# taktik.net
KiCad netlist of a schematic drawn in Altium Designer
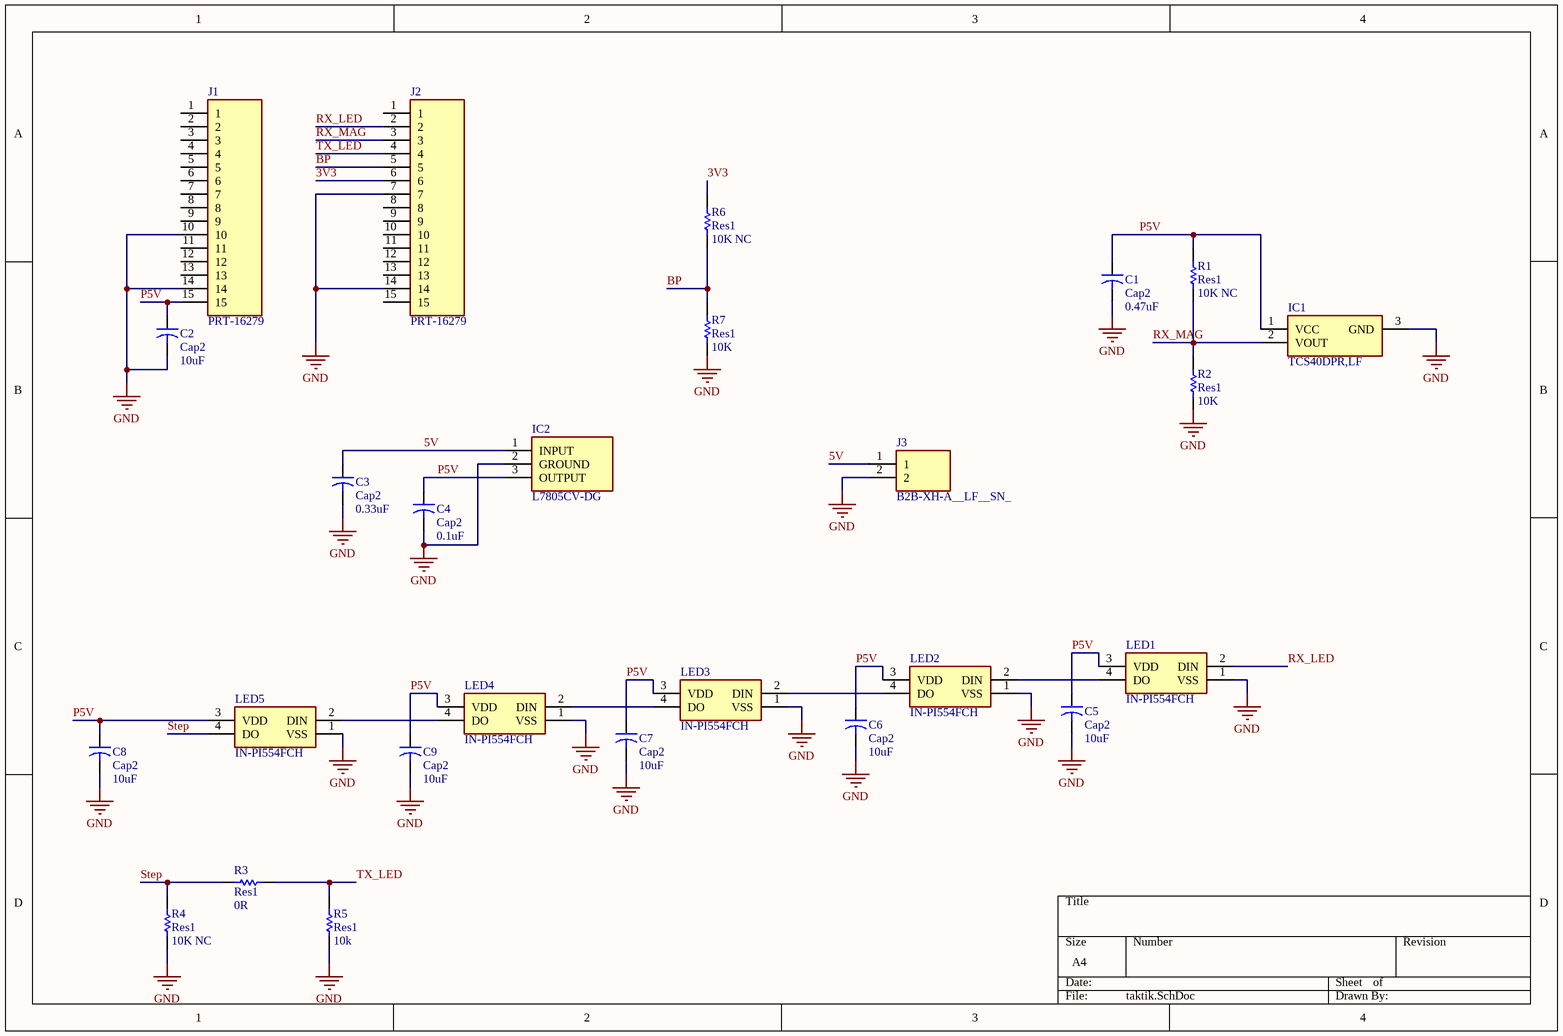
[diagram p0: taktik.SchDoc]

(export (version "E")
  (design (tool "Eeschema 10.0.6"))
  (components
    (comp (ref "C1")
      (value "Cap2")
      (footprint "CAPR5-4X5")
      (description "Capacitor")
      (fields (field (name "ALTIUM_VALUE") "0.47uF") (field (name "PUBLISHER") "Altium Limited"))
      (libsource (lib "Miscellaneous Devices") (part "Cap2"))
    )
    (comp (ref "C2")
      (value "Cap2")
      (footprint "CAPR5-4X5")
      (description "Capacitor")
      (fields (field (name "ALTIUM_VALUE") "10uF") (field (name "PUBLISHER") "Altium Limited"))
      (libsource (lib "Miscellaneous Devices") (part "Cap2"))
    )
    (comp (ref "C3")
      (value "Cap2")
      (footprint "CAPR5-4X5")
      (description "Capacitor")
      (fields (field (name "ALTIUM_VALUE") "0.33uF") (field (name "PUBLISHER") "Altium Limited"))
      (libsource (lib "Miscellaneous Devices") (part "Cap2"))
    )
    (comp (ref "C4")
      (value "Cap2")
      (footprint "CAPR5-4X5")
      (description "Capacitor")
      (fields (field (name "ALTIUM_VALUE") "0.1uF") (field (name "PUBLISHER") "Altium Limited"))
      (libsource (lib "Miscellaneous Devices") (part "Cap2"))
    )
    (comp (ref "C5")
      (value "Cap2")
      (footprint "CAPR5-4X5")
      (description "Capacitor")
      (fields (field (name "ALTIUM_VALUE") "10uF") (field (name "PUBLISHER") "Altium Limited"))
      (libsource (lib "Miscellaneous Devices") (part "Cap2"))
    )
    (comp (ref "C6")
      (value "Cap2")
      (footprint "CAPR5-4X5")
      (description "Capacitor")
      (fields (field (name "ALTIUM_VALUE") "10uF") (field (name "PUBLISHER") "Altium Limited"))
      (libsource (lib "Miscellaneous Devices") (part "Cap2"))
    )
    (comp (ref "C7")
      (value "Cap2")
      (footprint "CAPR5-4X5")
      (description "Capacitor")
      (fields (field (name "ALTIUM_VALUE") "10uF") (field (name "PUBLISHER") "Altium Limited"))
      (libsource (lib "Miscellaneous Devices") (part "Cap2"))
    )
    (comp (ref "C8")
      (value "Cap2")
      (footprint "CAPR5-4X5")
      (description "Capacitor")
      (fields (field (name "ALTIUM_VALUE") "10uF") (field (name "PUBLISHER") "Altium Limited"))
      (libsource (lib "Miscellaneous Devices") (part "Cap2"))
    )
    (comp (ref "C9")
      (value "Cap2")
      (footprint "CAPR5-4X5")
      (description "Capacitor")
      (fields (field (name "ALTIUM_VALUE") "10uF") (field (name "PUBLISHER") "Altium Limited"))
      (libsource (lib "Miscellaneous Devices") (part "Cap2"))
    )
    (comp (ref "IC1")
      (value "TCS40DPR,LF")
      (footprint "SamacSys:SOTFL95P240X88-3N")
      (description "Integrated Circuit")
      (fields (field (name "MOUSER PART NUMBER") "757-TCS40DPRLF"))
      (libsource (lib "*") (part "TCS40DPR,LF"))
    )
    (comp (ref "IC2")
      (value "L7805CV-DG")
      (footprint "SamacSys:TO255P460X1020X2008-3P")
      (description "Integrated Circuit")
      (fields (field (name "MOUSER PART NUMBER") "511-L7805CV-DG"))
      (libsource (lib "*") (part "L7805CV-DG"))
    )
    (comp (ref "J1")
      (value "PRT-16279")
      (footprint "SamacSys:PRT16279")
      (description "Connector")
      (libsource (lib "*") (part "PRT-16279"))
    )
    (comp (ref "J2")
      (value "PRT-16279")
      (footprint "SamacSys:PRT16279")
      (description "Connector")
      (libsource (lib "*") (part "PRT-16279"))
    )
    (comp (ref "J3")
      (value "B2B-XH-A__LF__SN_")
      (footprint "SamacSys:SHDR2W64P0X250_1X2_740X575X700P")
      (description "Connector")
      (fields (field (name "MANUFACTURER_PART_NUMBER") "B2B-XH-A (LF)(SN)"))
      (libsource (lib "*") (part "B2B-XH-A__LF__SN_"))
    )
    (comp (ref "LED1")
      (value "IN-PI554FCH")
      (footprint "SamacSys:INPI554FCH")
      (description "LED")
      (fields (field (name "MOUSER PART NUMBER") "743-IN-PI554FCH"))
      (libsource (lib "*") (part "IN-PI554FCH"))
    )
    (comp (ref "LED2")
      (value "IN-PI554FCH")
      (footprint "SamacSys:INPI554FCH")
      (description "LED")
      (fields (field (name "MOUSER PART NUMBER") "743-IN-PI554FCH"))
      (libsource (lib "*") (part "IN-PI554FCH"))
    )
    (comp (ref "LED3")
      (value "IN-PI554FCH")
      (footprint "SamacSys:INPI554FCH")
      (description "LED")
      (fields (field (name "MOUSER PART NUMBER") "743-IN-PI554FCH"))
      (libsource (lib "*") (part "IN-PI554FCH"))
    )
    (comp (ref "LED4")
      (value "IN-PI554FCH")
      (footprint "SamacSys:INPI554FCH")
      (description "LED")
      (fields (field (name "MOUSER PART NUMBER") "743-IN-PI554FCH"))
      (libsource (lib "*") (part "IN-PI554FCH"))
    )
    (comp (ref "LED5")
      (value "IN-PI554FCH")
      (footprint "SamacSys:INPI554FCH")
      (description "LED")
      (fields (field (name "MOUSER PART NUMBER") "743-IN-PI554FCH"))
      (libsource (lib "*") (part "IN-PI554FCH"))
    )
    (comp (ref "R1")
      (value "Res1")
      (footprint "AXIAL-0.3")
      (description "Resistor")
      (fields (field (name "ALTIUM_VALUE") "10K NC") (field (name "PUBLISHER") "Altium Limited"))
      (libsource (lib "Miscellaneous Devices") (part "Res1"))
    )
    (comp (ref "R2")
      (value "Res1")
      (footprint "AXIAL-0.3")
      (description "Resistor")
      (fields (field (name "ALTIUM_VALUE") "10K") (field (name "PUBLISHER") "Altium Limited"))
      (libsource (lib "Miscellaneous Devices") (part "Res1"))
    )
    (comp (ref "R3")
      (value "Res1")
      (footprint "AXIAL-0.3")
      (description "Resistor")
      (fields (field (name "ALTIUM_VALUE") "0R") (field (name "PUBLISHER") "Altium Limited"))
      (libsource (lib "Miscellaneous Devices") (part "Res1"))
    )
    (comp (ref "R4")
      (value "Res1")
      (footprint "AXIAL-0.3")
      (description "Resistor")
      (fields (field (name "ALTIUM_VALUE") "10K NC") (field (name "PUBLISHER") "Altium Limited"))
      (libsource (lib "Miscellaneous Devices") (part "Res1"))
    )
    (comp (ref "R5")
      (value "Res1")
      (footprint "AXIAL-0.3")
      (description "Resistor")
      (fields (field (name "ALTIUM_VALUE") "10k") (field (name "PUBLISHER") "Altium Limited"))
      (libsource (lib "Miscellaneous Devices") (part "Res1"))
    )
    (comp (ref "R6")
      (value "Res1")
      (footprint "AXIAL-0.3")
      (description "Resistor")
      (fields (field (name "ALTIUM_VALUE") "10K NC") (field (name "PUBLISHER") "Altium Limited"))
      (libsource (lib "Miscellaneous Devices") (part "Res1"))
    )
    (comp (ref "R7")
      (value "Res1")
      (footprint "AXIAL-0.3")
      (description "Resistor")
      (fields (field (name "ALTIUM_VALUE") "10K") (field (name "PUBLISHER") "Altium Limited"))
      (libsource (lib "Miscellaneous Devices") (part "Res1"))
    )
  )
  (nets
    (net (code "1") (name "/3V3") (class "Default")
      (node (ref "J2") (pin "6") (pinfunction "6_6") (pintype "passive"))
      (node (ref "R6") (pin "1") (pinfunction "1_1") (pintype "passive"))
    )
    (net (code "2") (name "/5V") (class "Default")
      (node (ref "C3") (pin "1") (pinfunction "1_1") (pintype "passive"))
      (node (ref "IC2") (pin "1") (pinfunction "INPUT_1") (pintype "passive"))
      (node (ref "J3") (pin "1") (pinfunction "1_1") (pintype "passive"))
    )
    (net (code "3") (name "/BP") (class "Default")
      (node (ref "J2") (pin "5") (pinfunction "5_5") (pintype "passive"))
      (node (ref "R6") (pin "2") (pinfunction "2_2") (pintype "passive"))
      (node (ref "R7") (pin "1") (pinfunction "1_1") (pintype "passive"))
    )
    (net (code "4") (name "/P5V") (class "Default")
      (node (ref "C1") (pin "1") (pinfunction "1_1") (pintype "passive"))
      (node (ref "C2") (pin "1") (pinfunction "1_1") (pintype "passive"))
      (node (ref "C4") (pin "1") (pinfunction "1_1") (pintype "passive"))
      (node (ref "C5") (pin "1") (pinfunction "1_1") (pintype "passive"))
      (node (ref "C6") (pin "1") (pinfunction "1_1") (pintype "passive"))
      (node (ref "C7") (pin "1") (pinfunction "1_1") (pintype "passive"))
      (node (ref "C8") (pin "1") (pinfunction "1_1") (pintype "passive"))
      (node (ref "C9") (pin "1") (pinfunction "1_1") (pintype "passive"))
      (node (ref "IC1") (pin "1") (pinfunction "VCC_1") (pintype "passive"))
      (node (ref "IC2") (pin "3") (pinfunction "OUTPUT_3") (pintype "passive"))
      (node (ref "J1") (pin "15") (pinfunction "15_15") (pintype "passive"))
      (node (ref "LED1") (pin "3") (pinfunction "VDD_3") (pintype "passive"))
      (node (ref "LED2") (pin "3") (pinfunction "VDD_3") (pintype "passive"))
      (node (ref "LED3") (pin "3") (pinfunction "VDD_3") (pintype "passive"))
      (node (ref "LED4") (pin "3") (pinfunction "VDD_3") (pintype "passive"))
      (node (ref "LED5") (pin "3") (pinfunction "VDD_3") (pintype "passive"))
      (node (ref "R1") (pin "1") (pinfunction "1_1") (pintype "passive"))
    )
    (net (code "5") (name "/RX_LED") (class "Default")
      (node (ref "J2") (pin "2") (pinfunction "2_2") (pintype "passive"))
      (node (ref "LED1") (pin "2") (pinfunction "DIN_2") (pintype "passive"))
    )
    (net (code "6") (name "/RX_MAG") (class "Default")
      (node (ref "IC1") (pin "2") (pinfunction "VOUT_2") (pintype "passive"))
      (node (ref "J2") (pin "3") (pinfunction "3_3") (pintype "passive"))
      (node (ref "R1") (pin "2") (pinfunction "2_2") (pintype "passive"))
      (node (ref "R2") (pin "1") (pinfunction "1_1") (pintype "passive"))
    )
    (net (code "7") (name "/Step") (class "Default")
      (node (ref "LED5") (pin "4") (pinfunction "DO_4") (pintype "passive"))
      (node (ref "R3") (pin "1") (pinfunction "1_1") (pintype "passive"))
      (node (ref "R4") (pin "1") (pinfunction "1_1") (pintype "passive"))
    )
    (net (code "8") (name "/TX_LED") (class "Default")
      (node (ref "J2") (pin "4") (pinfunction "4_4") (pintype "passive"))
      (node (ref "R3") (pin "2") (pinfunction "2_2") (pintype "passive"))
      (node (ref "R5") (pin "1") (pinfunction "1_1") (pintype "passive"))
    )
    (net (code "9") (name "GND") (class "Default")
      (node (ref "C1") (pin "2") (pinfunction "2_2") (pintype "passive"))
      (node (ref "C2") (pin "2") (pinfunction "2_2") (pintype "passive"))
      (node (ref "C3") (pin "2") (pinfunction "2_2") (pintype "passive"))
      (node (ref "C4") (pin "2") (pinfunction "2_2") (pintype "passive"))
      (node (ref "C5") (pin "2") (pinfunction "2_2") (pintype "passive"))
      (node (ref "C6") (pin "2") (pinfunction "2_2") (pintype "passive"))
      (node (ref "C7") (pin "2") (pinfunction "2_2") (pintype "passive"))
      (node (ref "C8") (pin "2") (pinfunction "2_2") (pintype "passive"))
      (node (ref "C9") (pin "2") (pinfunction "2_2") (pintype "passive"))
      (node (ref "IC1") (pin "3") (pinfunction "GND_3") (pintype "passive"))
      (node (ref "IC2") (pin "2") (pinfunction "GROUND_2") (pintype "passive"))
      (node (ref "J1") (pin "10") (pinfunction "10_10") (pintype "passive"))
      (node (ref "J1") (pin "14") (pinfunction "14_14") (pintype "passive"))
      (node (ref "J2") (pin "14") (pinfunction "14_14") (pintype "passive"))
      (node (ref "J2") (pin "7") (pinfunction "7_7") (pintype "passive"))
      (node (ref "J3") (pin "2") (pinfunction "2_2") (pintype "passive"))
      (node (ref "LED1") (pin "1") (pinfunction "VSS_1") (pintype "passive"))
      (node (ref "LED2") (pin "1") (pinfunction "VSS_1") (pintype "passive"))
      (node (ref "LED3") (pin "1") (pinfunction "VSS_1") (pintype "passive"))
      (node (ref "LED4") (pin "1") (pinfunction "VSS_1") (pintype "passive"))
      (node (ref "LED5") (pin "1") (pinfunction "VSS_1") (pintype "passive"))
      (node (ref "R2") (pin "2") (pinfunction "2_2") (pintype "passive"))
      (node (ref "R4") (pin "2") (pinfunction "2_2") (pintype "passive"))
      (node (ref "R5") (pin "2") (pinfunction "2_2") (pintype "passive"))
      (node (ref "R7") (pin "2") (pinfunction "2_2") (pintype "passive"))
    )
    (net (code "10") (name "Net-(LED1-DO)") (class "Default")
      (node (ref "LED1") (pin "4") (pinfunction "DO_4") (pintype "passive"))
      (node (ref "LED2") (pin "2") (pinfunction "DIN_2") (pintype "passive"))
    )
    (net (code "11") (name "Net-(LED2-DO)") (class "Default")
      (node (ref "LED2") (pin "4") (pinfunction "DO_4") (pintype "passive"))
      (node (ref "LED3") (pin "2") (pinfunction "DIN_2") (pintype "passive"))
    )
    (net (code "12") (name "Net-(LED3-DO)") (class "Default")
      (node (ref "LED3") (pin "4") (pinfunction "DO_4") (pintype "passive"))
      (node (ref "LED4") (pin "2") (pinfunction "DIN_2") (pintype "passive"))
    )
    (net (code "13") (name "Net-(LED4-DO)") (class "Default")
      (node (ref "LED4") (pin "4") (pinfunction "DO_4") (pintype "passive"))
      (node (ref "LED5") (pin "2") (pinfunction "DIN_2") (pintype "passive"))
    )
    (net (code "14") (name "unconnected-(J1-Pad1)") (class "Default")
      (node (ref "J1") (pin "1") (pinfunction "1_1") (pintype "passive"))
    )
    (net (code "15") (name "unconnected-(J1-Pad2)") (class "Default")
      (node (ref "J1") (pin "2") (pinfunction "2_2") (pintype "passive"))
    )
    (net (code "16") (name "unconnected-(J1-Pad3)") (class "Default")
      (node (ref "J1") (pin "3") (pinfunction "3_3") (pintype "passive"))
    )
    (net (code "17") (name "unconnected-(J1-Pad4)") (class "Default")
      (node (ref "J1") (pin "4") (pinfunction "4_4") (pintype "passive"))
    )
    (net (code "18") (name "unconnected-(J1-Pad5)") (class "Default")
      (node (ref "J1") (pin "5") (pinfunction "5_5") (pintype "passive"))
    )
    (net (code "19") (name "unconnected-(J1-Pad6)") (class "Default")
      (node (ref "J1") (pin "6") (pinfunction "6_6") (pintype "passive"))
    )
    (net (code "20") (name "unconnected-(J1-Pad7)") (class "Default")
      (node (ref "J1") (pin "7") (pinfunction "7_7") (pintype "passive"))
    )
    (net (code "21") (name "unconnected-(J1-Pad8)") (class "Default")
      (node (ref "J1") (pin "8") (pinfunction "8_8") (pintype "passive"))
    )
    (net (code "22") (name "unconnected-(J1-Pad9)") (class "Default")
      (node (ref "J1") (pin "9") (pinfunction "9_9") (pintype "passive"))
    )
    (net (code "23") (name "unconnected-(J1-Pad11)") (class "Default")
      (node (ref "J1") (pin "11") (pinfunction "11_11") (pintype "passive"))
    )
    (net (code "24") (name "unconnected-(J1-Pad12)") (class "Default")
      (node (ref "J1") (pin "12") (pinfunction "12_12") (pintype "passive"))
    )
    (net (code "25") (name "unconnected-(J1-Pad13)") (class "Default")
      (node (ref "J1") (pin "13") (pinfunction "13_13") (pintype "passive"))
    )
    (net (code "26") (name "unconnected-(J2-Pad1)") (class "Default")
      (node (ref "J2") (pin "1") (pinfunction "1_1") (pintype "passive"))
    )
    (net (code "27") (name "unconnected-(J2-Pad8)") (class "Default")
      (node (ref "J2") (pin "8") (pinfunction "8_8") (pintype "passive"))
    )
    (net (code "28") (name "unconnected-(J2-Pad9)") (class "Default")
      (node (ref "J2") (pin "9") (pinfunction "9_9") (pintype "passive"))
    )
    (net (code "29") (name "unconnected-(J2-Pad10)") (class "Default")
      (node (ref "J2") (pin "10") (pinfunction "10_10") (pintype "passive"))
    )
    (net (code "30") (name "unconnected-(J2-Pad11)") (class "Default")
      (node (ref "J2") (pin "11") (pinfunction "11_11") (pintype "passive"))
    )
    (net (code "31") (name "unconnected-(J2-Pad12)") (class "Default")
      (node (ref "J2") (pin "12") (pinfunction "12_12") (pintype "passive"))
    )
    (net (code "32") (name "unconnected-(J2-Pad13)") (class "Default")
      (node (ref "J2") (pin "13") (pinfunction "13_13") (pintype "passive"))
    )
    (net (code "33") (name "unconnected-(J2-Pad15)") (class "Default")
      (node (ref "J2") (pin "15") (pinfunction "15_15") (pintype "passive"))
    )
  )
)
